# ser2can.net
KiCad netlist of a schematic drawn in EAGLE
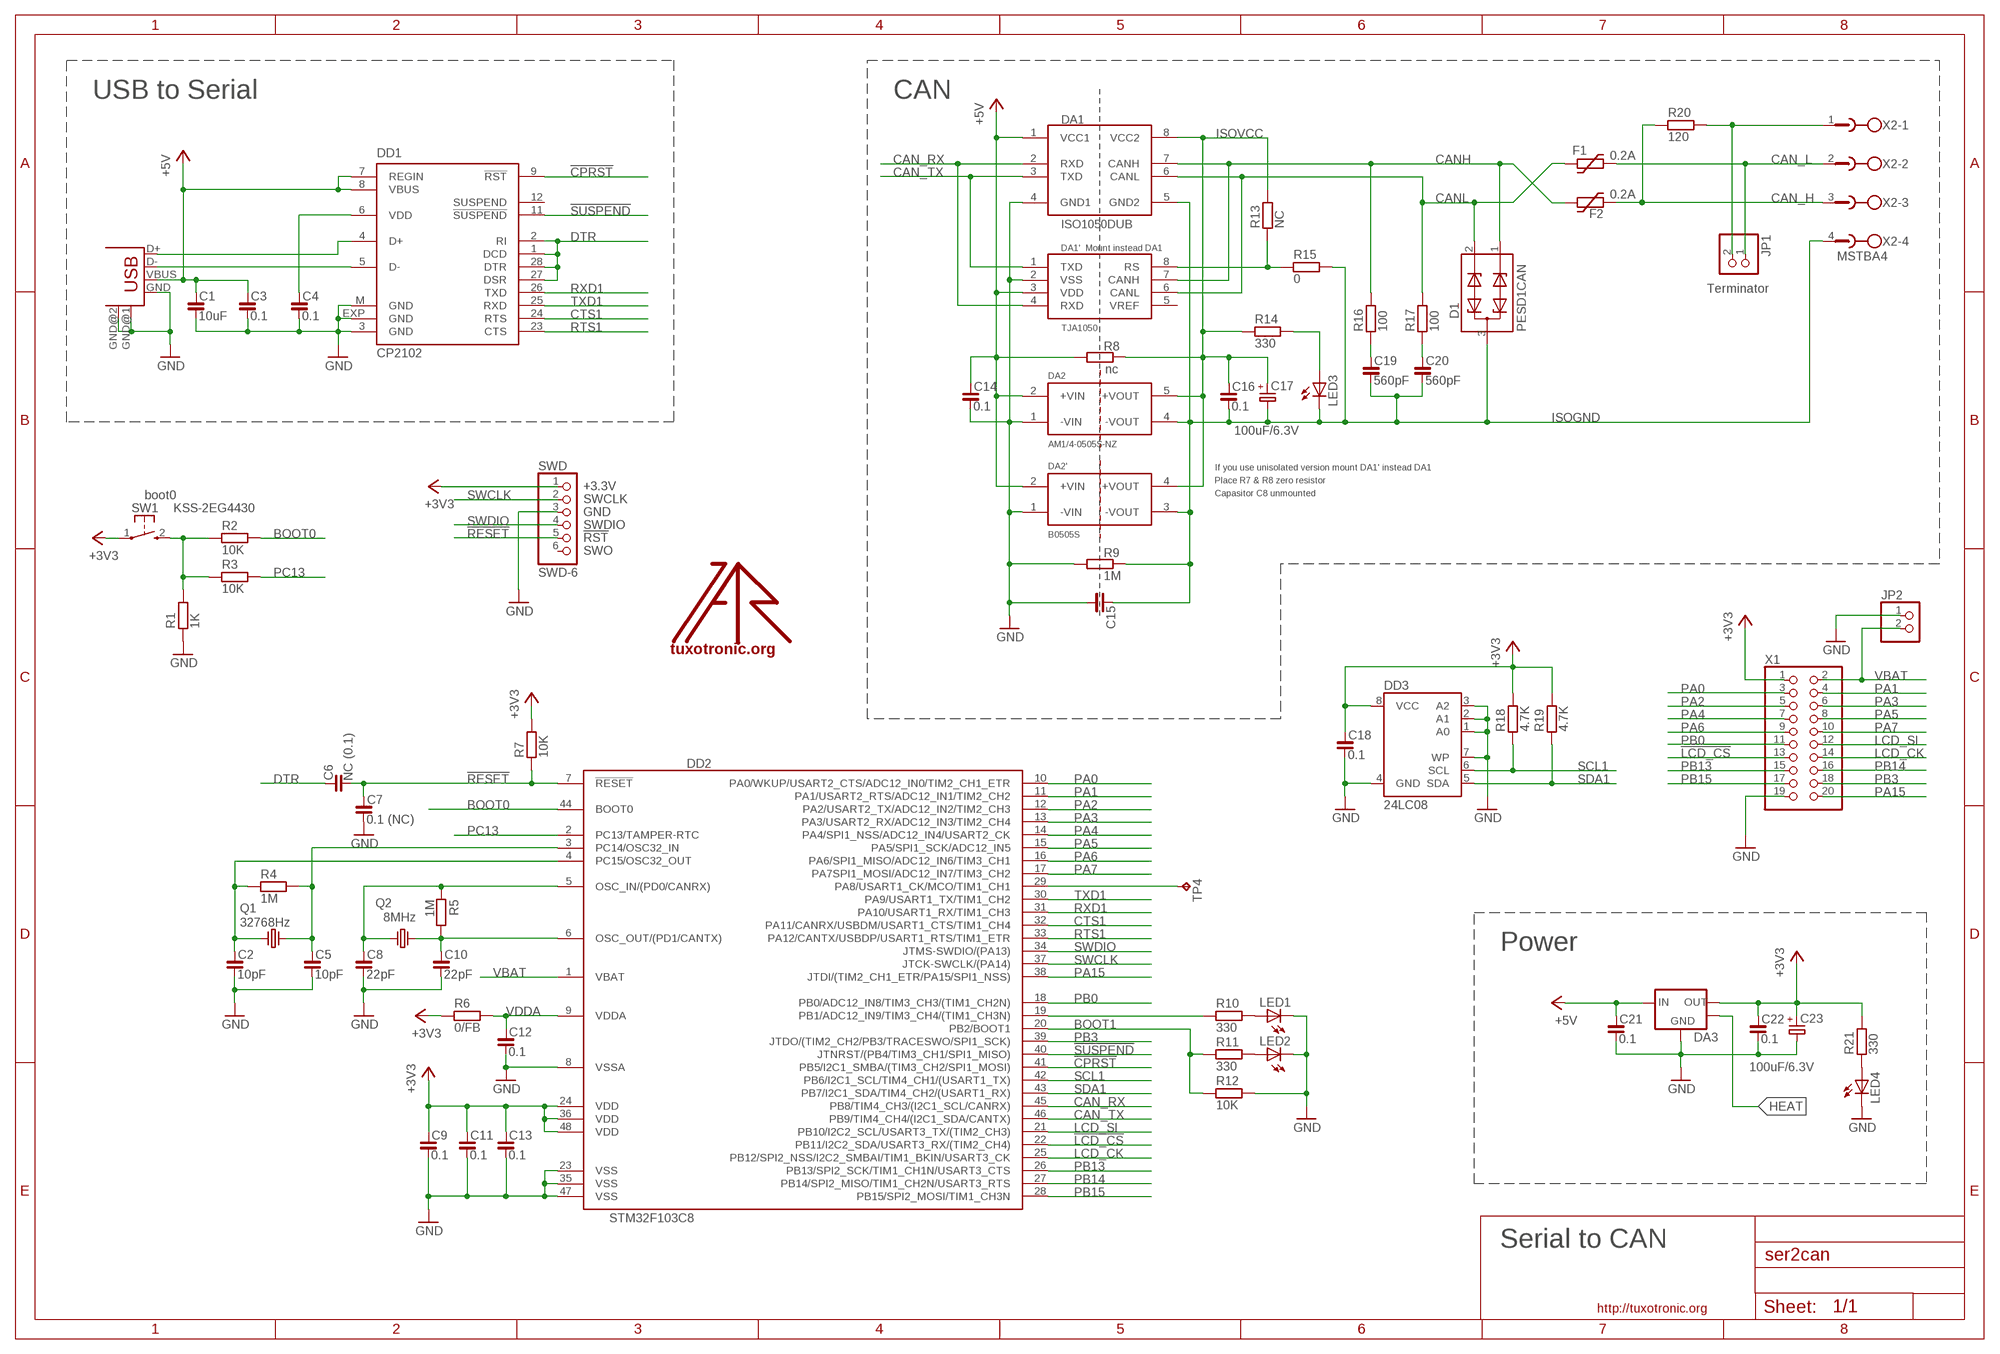
[diagram p0: schematic, sheet 1]

(export (version "E")
  (design (tool "Eeschema 10.0.6"))
  (components
    (comp (ref "C1")
      (value "10uF")
      (footprint "eagle-import:C0603")
      (libsource (lib "eagle-import") (part "rc-master-smd_C_0603"))
    )
    (comp (ref "C2")
      (value "10pF")
      (footprint "eagle-import:C0603")
      (libsource (lib "eagle-import") (part "rc-master-smd_C_0603"))
    )
    (comp (ref "C3")
      (value "0.1")
      (footprint "eagle-import:C0603")
      (libsource (lib "eagle-import") (part "rc-master-smd_C_0603"))
    )
    (comp (ref "C4")
      (value "0.1")
      (footprint "eagle-import:C0603")
      (libsource (lib "eagle-import") (part "rc-master-smd_C_0603"))
    )
    (comp (ref "C5")
      (value "10pF")
      (footprint "eagle-import:C0603")
      (libsource (lib "eagle-import") (part "rc-master-smd_C_0603"))
    )
    (comp (ref "C6")
      (value "NC (0.1)")
      (footprint "eagle-import:C0603")
      (libsource (lib "eagle-import") (part "rc-master-smd_C_0603"))
    )
    (comp (ref "C7")
      (value "0.1 (NC)")
      (footprint "eagle-import:C0603")
      (libsource (lib "eagle-import") (part "rc-master-smd_C_0603"))
    )
    (comp (ref "C8")
      (value "22pF")
      (footprint "eagle-import:C0603")
      (libsource (lib "eagle-import") (part "rc-master-smd_C_0603"))
    )
    (comp (ref "C9")
      (value "0.1")
      (footprint "eagle-import:C0603")
      (libsource (lib "eagle-import") (part "rc-master-smd_C_0603"))
    )
    (comp (ref "C10")
      (value "22pF")
      (footprint "eagle-import:C0603")
      (libsource (lib "eagle-import") (part "rc-master-smd_C_0603"))
    )
    (comp (ref "C11")
      (value "0.1")
      (footprint "eagle-import:C0603")
      (libsource (lib "eagle-import") (part "rc-master-smd_C_0603"))
    )
    (comp (ref "C12")
      (value "0.1")
      (footprint "eagle-import:C0603")
      (libsource (lib "eagle-import") (part "rc-master-smd_C_0603"))
    )
    (comp (ref "C13")
      (value "0.1")
      (footprint "eagle-import:C0603")
      (libsource (lib "eagle-import") (part "rc-master-smd_C_0603"))
    )
    (comp (ref "C14")
      (value "0.1")
      (footprint "eagle-import:C0603")
      (libsource (lib "eagle-import") (part "rc-master-smd_C_0603"))
    )
    (comp (ref "C15")
      (value "C_C050-110X055")
      (footprint "eagle-import:C050-110X055")
      (libsource (lib "eagle-import") (part "C_C050-110X055"))
    )
    (comp (ref "C16")
      (value "0.1")
      (footprint "eagle-import:C0603")
      (libsource (lib "eagle-import") (part "rc-master-smd_C_0603"))
    )
    (comp (ref "C17")
      (value "100uF/6.3V")
      (footprint "eagle-import:SMC_C")
      (libsource (lib "eagle-import") (part "CP_SMCC"))
    )
    (comp (ref "C18")
      (value "0.1")
      (footprint "eagle-import:C0603")
      (libsource (lib "eagle-import") (part "rc-master-smd_C_0603"))
    )
    (comp (ref "C19")
      (value "560pF")
      (footprint "eagle-import:C0603")
      (libsource (lib "eagle-import") (part "rc-master-smd_C_0603"))
    )
    (comp (ref "C20")
      (value "560pF")
      (footprint "eagle-import:C0603")
      (libsource (lib "eagle-import") (part "rc-master-smd_C_0603"))
    )
    (comp (ref "C21")
      (value "0.1")
      (footprint "eagle-import:C0805")
      (libsource (lib "eagle-import") (part "rc-master-smd_C_0805"))
    )
    (comp (ref "C22")
      (value "0.1")
      (footprint "eagle-import:C0805")
      (libsource (lib "eagle-import") (part "rc-master-smd_C_0805"))
    )
    (comp (ref "C23")
      (value "100uF/6.3V")
      (footprint "eagle-import:SMC_C")
      (libsource (lib "eagle-import") (part "CP_SMCC"))
    )
    (comp (ref "D1")
      (value "PESD1CAN")
      (footprint "eagle-import:SOT23")
      (libsource (lib "eagle-import") (part "PESD1CAN"))
    )
    (comp (ref "DA1")
      (value "ISO1050DUB")
      (footprint "eagle-import:DUB-8")
      (libsource (lib "eagle-import") (part "ISO1050DUB"))
    )
    (comp (ref "DA1'")
      (value "TJA1050")
      (footprint "eagle-import:SO08")
      (libsource (lib "eagle-import") (part "TJA1050"))
    )
    (comp (ref "DA2")
      (value "AM1/4-0505S-NZ")
      (footprint "eagle-import:AM1_4")
      (libsource (lib "eagle-import") (part "AM1/4--NZ0505S"))
    )
    (comp (ref "DA2'")
      (value "B0505S")
      (footprint "eagle-import:SIP4")
      (libsource (lib "eagle-import") (part "VA-S1"))
    )
    (comp (ref "DA3")
      (value "LM1117-3.3")
      (footprint "eagle-import:SOT223")
      (libsource (lib "eagle-import") (part "LM1117-3.3"))
    )
    (comp (ref "DD1")
      (value "CP2102")
      (footprint "eagle-import:MLP28")
      (libsource (lib "eagle-import") (part "CP2102"))
    )
    (comp (ref "DD2")
      (value "STM32F103C8")
      (footprint "eagle-import:LQFP48")
      (libsource (lib "eagle-import") (part "STM32F103C8"))
    )
    (comp (ref "DD3")
      (value "24LC08")
      (footprint "eagle-import:SO08")
      (libsource (lib "eagle-import") (part "AT24CS256"))
    )
    (comp (ref "F1")
      (value "0.2A")
      (footprint "eagle-import:1812L")
      (libsource (lib "eagle-import") (part "1812L"))
    )
    (comp (ref "F2")
      (value "0.2A")
      (footprint "eagle-import:1812L")
      (libsource (lib "eagle-import") (part "1812L"))
    )
    (comp (ref "JP1")
      (value "PINHD-1X2_2.54S")
      (footprint "eagle-import:1X02SMALL")
      (libsource (lib "eagle-import") (part "PINHD-1X2_2.54S"))
    )
    (comp (ref "JP2")
      (value "PINHD-1X2_2.00")
      (footprint "eagle-import:1X02M")
      (libsource (lib "eagle-import") (part "PINHD-1X2_2.00"))
    )
    (comp (ref "LED1")
      (value "LEDCHIPLED_0805")
      (footprint "eagle-import:CHIPLED_0805")
      (libsource (lib "eagle-import") (part "LEDCHIPLED_0805"))
    )
    (comp (ref "LED2")
      (value "LEDCHIPLED_0805")
      (footprint "eagle-import:CHIPLED_0805")
      (libsource (lib "eagle-import") (part "LEDCHIPLED_0805"))
    )
    (comp (ref "LED3")
      (value "LEDCHIPLED_0805")
      (footprint "eagle-import:CHIPLED_0805")
      (libsource (lib "eagle-import") (part "LEDCHIPLED_0805"))
    )
    (comp (ref "LED4")
      (value "LEDCHIPLED_0805")
      (footprint "eagle-import:CHIPLED_0805")
      (libsource (lib "eagle-import") (part "LEDCHIPLED_0805"))
    )
    (comp (ref "Q1")
      (value "32768Hz")
      (footprint "eagle-import:MM20SS")
      (libsource (lib "eagle-import") (part "CRYSTAL-MM20SS"))
    )
    (comp (ref "Q2")
      (value "8MHz")
      (footprint "eagle-import:HC49_S")
      (libsource (lib "eagle-import") (part "CRYSTAL-HC49S"))
    )
    (comp (ref "R1")
      (value "1K")
      (footprint "eagle-import:R0603")
      (libsource (lib "eagle-import") (part "R_0603"))
    )
    (comp (ref "R2")
      (value "10K")
      (footprint "eagle-import:R0603")
      (libsource (lib "eagle-import") (part "R_0603"))
    )
    (comp (ref "R3")
      (value "10K")
      (footprint "eagle-import:R0603")
      (libsource (lib "eagle-import") (part "R_0603"))
    )
    (comp (ref "R4")
      (value "1M")
      (footprint "eagle-import:R0603")
      (libsource (lib "eagle-import") (part "R_0603"))
    )
    (comp (ref "R5")
      (value "1M")
      (footprint "eagle-import:R0603")
      (libsource (lib "eagle-import") (part "R_0603"))
    )
    (comp (ref "R6")
      (value "0/FB")
      (footprint "eagle-import:R0603")
      (libsource (lib "eagle-import") (part "R_0603"))
    )
    (comp (ref "R7")
      (value "10K")
      (footprint "eagle-import:R0603")
      (libsource (lib "eagle-import") (part "R_0603"))
    )
    (comp (ref "R8")
      (value "nc")
      (footprint "eagle-import:R1206")
      (libsource (lib "eagle-import") (part "R_1206"))
    )
    (comp (ref "R9")
      (value "1M")
      (footprint "eagle-import:R1206")
      (libsource (lib "eagle-import") (part "R_1206"))
    )
    (comp (ref "R10")
      (value "330")
      (footprint "eagle-import:R0603")
      (libsource (lib "eagle-import") (part "R_0603"))
    )
    (comp (ref "R11")
      (value "330")
      (footprint "eagle-import:R0603")
      (libsource (lib "eagle-import") (part "R_0603"))
    )
    (comp (ref "R12")
      (value "10K")
      (footprint "eagle-import:R0603")
      (libsource (lib "eagle-import") (part "R_0603"))
    )
    (comp (ref "R13")
      (value "NC")
      (footprint "eagle-import:R0603")
      (libsource (lib "eagle-import") (part "R_0603"))
    )
    (comp (ref "R14")
      (value "330")
      (footprint "eagle-import:R0603")
      (libsource (lib "eagle-import") (part "R_0603"))
    )
    (comp (ref "R15")
      (value "0")
      (footprint "eagle-import:R0603")
      (libsource (lib "eagle-import") (part "R_0603"))
    )
    (comp (ref "R16")
      (value "100")
      (footprint "eagle-import:R0603")
      (libsource (lib "eagle-import") (part "R_0603"))
    )
    (comp (ref "R17")
      (value "100")
      (footprint "eagle-import:R0603")
      (libsource (lib "eagle-import") (part "R_0603"))
    )
    (comp (ref "R18")
      (value "4.7K")
      (footprint "eagle-import:R0603")
      (libsource (lib "eagle-import") (part "R_0603"))
    )
    (comp (ref "R19")
      (value "4.7K")
      (footprint "eagle-import:R0603")
      (libsource (lib "eagle-import") (part "R_0603"))
    )
    (comp (ref "R20")
      (value "120")
      (footprint "eagle-import:R0805")
      (libsource (lib "eagle-import") (part "R_0805"))
    )
    (comp (ref "R21")
      (value "330")
      (footprint "eagle-import:R0603")
      (libsource (lib "eagle-import") (part "R_0603"))
    )
    (comp (ref "SW1")
      (value "KSS-2EG4430")
      (footprint "eagle-import:KSS-2EG4430")
      (libsource (lib "eagle-import") (part "KSS-2EG4430"))
    )
    (comp (ref "SWD")
      (value "SWD-6")
      (footprint "eagle-import:JTAG6PIN")
      (libsource (lib "eagle-import") (part "SWD-6"))
    )
    (comp (ref "TP4")
      (value "TPB1,27")
      (footprint "eagle-import:B1,27")
      (libsource (lib "eagle-import") (part "TPB1,27"))
    )
    (comp (ref "U$")
      (value "LOGO")
      (footprint "eagle-import:TT_LOGO")
      (libsource (lib "eagle-import") (part "LOGO"))
    )
    (comp (ref "USB1")
      (value "USB-B-H")
      (footprint "eagle-import:USB-B-H")
      (libsource (lib "eagle-import") (part "USB-B-H"))
    )
    (comp (ref "X1")
      (value "PINHD-2X10_2.54")
      (footprint "eagle-import:2X10")
      (libsource (lib "eagle-import") (part "PINHD-2X10_2.54"))
    )
    (comp (ref "X2")
      (value "MSTBA4")
      (footprint "eagle-import:MSTBA4")
      (libsource (lib "eagle-import") (part "MSTBA4"))
    )
  )
  (nets
    (net (code "1") (name "+3V3") (class "Default")
      (node (ref "C11") (pin "1") (pinfunction "1_1") (pintype "passive"))
      (node (ref "C13") (pin "1") (pinfunction "1_1") (pintype "passive"))
      (node (ref "C18") (pin "1") (pinfunction "1_1") (pintype "passive"))
      (node (ref "C22") (pin "1") (pinfunction "1_1") (pintype "passive"))
      (node (ref "C23") (pin "+") (pinfunction "+_+") (pintype "passive"))
      (node (ref "C9") (pin "1") (pinfunction "1_1") (pintype "passive"))
      (node (ref "DA3") (pin "2") (pinfunction "OUT_2") (pintype "output"))
      (node (ref "DD2") (pin "24") (pinfunction "VDD_24") (pintype "power_in"))
      (node (ref "DD2") (pin "36") (pinfunction "VDD_36") (pintype "power_in"))
      (node (ref "DD2") (pin "48") (pinfunction "VDD_48") (pintype "power_in"))
      (node (ref "DD3") (pin "8") (pinfunction "VCC_8") (pintype "power_in"))
      (node (ref "R18") (pin "2") (pinfunction "2_2") (pintype "passive"))
      (node (ref "R19") (pin "2") (pinfunction "2_2") (pintype "passive"))
      (node (ref "R21") (pin "2") (pinfunction "2_2") (pintype "passive"))
      (node (ref "R6") (pin "1") (pinfunction "1_1") (pintype "passive"))
      (node (ref "R7") (pin "2") (pinfunction "2_2") (pintype "passive"))
      (node (ref "SW1") (pin "1") (pinfunction "P_1") (pintype "passive"))
      (node (ref "SWD") (pin "1") (pinfunction "1_1") (pintype "passive"))
      (node (ref "X1") (pin "1") (pinfunction "1_1") (pintype "passive"))
    )
    (net (code "2") (name "+5V") (class "Default")
      (node (ref "C1") (pin "1") (pinfunction "1_1") (pintype "passive"))
      (node (ref "C14") (pin "1") (pinfunction "1_1") (pintype "passive"))
      (node (ref "C21") (pin "1") (pinfunction "1_1") (pintype "passive"))
      (node (ref "C3") (pin "1") (pinfunction "1_1") (pintype "passive"))
      (node (ref "DA1") (pin "1") (pinfunction "VCC1_1") (pintype "power_in"))
      (node (ref "DA1'") (pin "3") (pinfunction "VDD_3") (pintype "power_in"))
      (node (ref "DA2") (pin "2") (pinfunction "+VIN_2") (pintype "power_in"))
      (node (ref "DA2'") (pin "2") (pinfunction "+VIN_2") (pintype "power_in"))
      (node (ref "DA3") (pin "3") (pinfunction "IN_3") (pintype "power_in"))
      (node (ref "DD1") (pin "7") (pinfunction "REGIN_7") (pintype "passive"))
      (node (ref "DD1") (pin "8") (pinfunction "VBUS_8") (pintype "input"))
      (node (ref "R8") (pin "1") (pinfunction "1_1") (pintype "passive"))
      (node (ref "USB1") (pin "VBUS") (pinfunction "VBUS_VBUS") (pintype "bidirectional"))
    )
    (net (code "3") (name "/BOOT0") (class "Default")
      (node (ref "DD2") (pin "44") (pinfunction "BOOT0_44") (pintype "input"))
      (node (ref "R2") (pin "2") (pinfunction "2_2") (pintype "passive"))
    )
    (net (code "4") (name "/BOOT1") (class "Default")
      (node (ref "DD2") (pin "20") (pinfunction "PB2/BOOT1_20") (pintype "bidirectional"))
      (node (ref "R11") (pin "1") (pinfunction "1_1") (pintype "passive"))
      (node (ref "R12") (pin "1") (pinfunction "1_1") (pintype "passive"))
    )
    (net (code "5") (name "/CANH") (class "Default")
      (node (ref "D1") (pin "1") (pinfunction "1_1") (pintype "passive"))
      (node (ref "DA1") (pin "7") (pinfunction "CANH_7") (pintype "bidirectional"))
      (node (ref "DA1'") (pin "7") (pinfunction "CANH_7") (pintype "bidirectional"))
      (node (ref "F2") (pin "P$1") (pinfunction "1_P$1") (pintype "passive"))
      (node (ref "R16") (pin "2") (pinfunction "2_2") (pintype "passive"))
    )
    (net (code "6") (name "/CANL") (class "Default")
      (node (ref "D1") (pin "2") (pinfunction "2_2") (pintype "passive"))
      (node (ref "DA1") (pin "6") (pinfunction "CANL_6") (pintype "bidirectional"))
      (node (ref "DA1'") (pin "6") (pinfunction "CANL_6") (pintype "bidirectional"))
      (node (ref "F1") (pin "P$1") (pinfunction "1_P$1") (pintype "passive"))
      (node (ref "R17") (pin "2") (pinfunction "2_2") (pintype "passive"))
    )
    (net (code "7") (name "/CAN_H") (class "Default")
      (node (ref "F2") (pin "P$2") (pinfunction "2_P$2") (pintype "passive"))
      (node (ref "R20") (pin "1") (pinfunction "1_1") (pintype "passive"))
      (node (ref "X2") (pin "3") (pinfunction "1_3") (pintype "passive"))
    )
    (net (code "8") (name "/CAN_L") (class "Default")
      (node (ref "F1") (pin "P$2") (pinfunction "2_P$2") (pintype "passive"))
      (node (ref "JP1") (pin "1") (pinfunction "1_1") (pintype "passive"))
      (node (ref "X2") (pin "2") (pinfunction "1_2") (pintype "passive"))
    )
    (net (code "9") (name "/CAN_RX") (class "Default")
      (node (ref "DA1") (pin "2") (pinfunction "RXD_2") (pintype "output"))
      (node (ref "DA1'") (pin "4") (pinfunction "RXD_4") (pintype "output"))
      (node (ref "DD2") (pin "45") (pinfunction "PB8/TIM4_CH3/(I2C1_SCL/CANRX)_45") (pintype "bidirectional"))
    )
    (net (code "10") (name "/CAN_TX") (class "Default")
      (node (ref "DA1") (pin "3") (pinfunction "TXD_3") (pintype "input"))
      (node (ref "DA1'") (pin "1") (pinfunction "TXD_1") (pintype "input"))
      (node (ref "DD2") (pin "46") (pinfunction "PB9/TIM4_CH4/(I2C1_SDA/CANTX)_46") (pintype "bidirectional"))
    )
    (net (code "11") (name "/CTS1") (class "Default")
      (node (ref "DD1") (pin "24") (pinfunction "RTS_24") (pintype "output"))
      (node (ref "DD2") (pin "32") (pinfunction "PA11/CANRX/USBDM/USART1_CTS/TIM1_CH4_32") (pintype "bidirectional"))
    )
    (net (code "12") (name "/DTR") (class "Default")
      (node (ref "C6") (pin "1") (pinfunction "1_1") (pintype "passive"))
      (node (ref "DD1") (pin "1") (pinfunction "DCD_1") (pintype "input"))
      (node (ref "DD1") (pin "2") (pinfunction "RI_2") (pintype "input"))
      (node (ref "DD1") (pin "27") (pinfunction "DSR_27") (pintype "input"))
      (node (ref "DD1") (pin "28") (pinfunction "DTR_28") (pintype "output"))
    )
    (net (code "13") (name "/ISOGND") (class "Default")
      (node (ref "C15") (pin "1") (pinfunction "1_1") (pintype "passive"))
      (node (ref "C16") (pin "2") (pinfunction "2_2") (pintype "passive"))
      (node (ref "C17") (pin "-") (pinfunction "-_-") (pintype "passive"))
      (node (ref "C19") (pin "2") (pinfunction "2_2") (pintype "passive"))
      (node (ref "C20") (pin "2") (pinfunction "2_2") (pintype "passive"))
      (node (ref "D1") (pin "3") (pinfunction "3_3") (pintype "passive"))
      (node (ref "DA1") (pin "5") (pinfunction "GND2_5") (pintype "power_in"))
      (node (ref "DA2") (pin "4") (pinfunction "-VOUT_4") (pintype "passive"))
      (node (ref "DA2'") (pin "3") (pinfunction "-VOUT_3") (pintype "passive"))
      (node (ref "LED3") (pin "C") (pinfunction "C_C") (pintype "passive"))
      (node (ref "R15") (pin "2") (pinfunction "2_2") (pintype "passive"))
      (node (ref "R9") (pin "2") (pinfunction "2_2") (pintype "passive"))
      (node (ref "X2") (pin "4") (pinfunction "1_4") (pintype "passive"))
    )
    (net (code "14") (name "/ISOVCC") (class "Default")
      (node (ref "C16") (pin "1") (pinfunction "1_1") (pintype "passive"))
      (node (ref "C17") (pin "+") (pinfunction "+_+") (pintype "passive"))
      (node (ref "DA1") (pin "8") (pinfunction "VCC2_8") (pintype "power_in"))
      (node (ref "DA2") (pin "5") (pinfunction "+VOUT_5") (pintype "passive"))
      (node (ref "DA2'") (pin "4") (pinfunction "+VOUT_4") (pintype "passive"))
      (node (ref "R13") (pin "2") (pinfunction "2_2") (pintype "passive"))
      (node (ref "R14") (pin "1") (pinfunction "1_1") (pintype "passive"))
      (node (ref "R8") (pin "2") (pinfunction "2_2") (pintype "passive"))
    )
    (net (code "15") (name "/LCD_CK") (class "Default")
      (node (ref "DD2") (pin "25") (pinfunction "PB12/SPI2_NSS/I2C2_SMBAI/TIM1_BKIN/USART3_CK_25") (pintype "bidirectional"))
      (node (ref "X1") (pin "14") (pinfunction "14_14") (pintype "passive"))
    )
    (net (code "16") (name "/LCD_SI") (class "Default")
      (node (ref "DD2") (pin "21") (pinfunction "PB10/I2C2_SCL/USART3_TX/(TIM2_CH3)_21") (pintype "bidirectional"))
      (node (ref "X1") (pin "12") (pinfunction "12_12") (pintype "passive"))
    )
    (net (code "17") (name "/PA0") (class "Default")
      (node (ref "DD2") (pin "10") (pinfunction "PA0/WKUP/USART2_CTS/ADC12_IN0/TIM2_CH1_ETR_10") (pintype "bidirectional"))
      (node (ref "X1") (pin "3") (pinfunction "3_3") (pintype "passive"))
    )
    (net (code "18") (name "/PA1") (class "Default")
      (node (ref "DD2") (pin "11") (pinfunction "PA1/USART2_RTS/ADC12_IN1/TIM2_CH2_11") (pintype "bidirectional"))
      (node (ref "X1") (pin "4") (pinfunction "4_4") (pintype "passive"))
    )
    (net (code "19") (name "/PA2") (class "Default")
      (node (ref "DD2") (pin "12") (pinfunction "PA2/USART2_TX/ADC12_IN2/TIM2_CH3_12") (pintype "bidirectional"))
      (node (ref "X1") (pin "5") (pinfunction "5_5") (pintype "passive"))
    )
    (net (code "20") (name "/PA3") (class "Default")
      (node (ref "DD2") (pin "13") (pinfunction "PA3/USART2_RX/ADC12_IN3/TIM2_CH4_13") (pintype "bidirectional"))
      (node (ref "X1") (pin "6") (pinfunction "6_6") (pintype "passive"))
    )
    (net (code "21") (name "/PA4") (class "Default")
      (node (ref "DD2") (pin "14") (pinfunction "PA4/SPI1_NSS/ADC12_IN4/USART2_CK_14") (pintype "bidirectional"))
      (node (ref "X1") (pin "7") (pinfunction "7_7") (pintype "passive"))
    )
    (net (code "22") (name "/PA5") (class "Default")
      (node (ref "DD2") (pin "15") (pinfunction "PA5/SPI1_SCK/ADC12_IN5_15") (pintype "bidirectional"))
      (node (ref "X1") (pin "8") (pinfunction "8_8") (pintype "passive"))
    )
    (net (code "23") (name "/PA6") (class "Default")
      (node (ref "DD2") (pin "16") (pinfunction "PA6/SPI1_MISO/ADC12_IN6/TIM3_CH1_16") (pintype "bidirectional"))
      (node (ref "X1") (pin "9") (pinfunction "9_9") (pintype "passive"))
    )
    (net (code "24") (name "/PA7") (class "Default")
      (node (ref "DD2") (pin "17") (pinfunction "PA7SPI1_MOSI/ADC12_IN7/TIM3_CH2_17") (pintype "bidirectional"))
      (node (ref "X1") (pin "10") (pinfunction "10_10") (pintype "passive"))
    )
    (net (code "25") (name "/PA15") (class "Default")
      (node (ref "DD2") (pin "38") (pinfunction "JTDI/(TIM2_CH1_ETR/PA15/SPI1_NSS)_38") (pintype "bidirectional"))
      (node (ref "X1") (pin "20") (pinfunction "20_20") (pintype "passive"))
    )
    (net (code "26") (name "/PB0") (class "Default")
      (node (ref "DD2") (pin "18") (pinfunction "PB0/ADC12_IN8/TIM3_CH3/(TIM1_CH2N)_18") (pintype "bidirectional"))
      (node (ref "X1") (pin "11") (pinfunction "11_11") (pintype "passive"))
    )
    (net (code "27") (name "/PB3") (class "Default")
      (node (ref "DD2") (pin "39") (pinfunction "JTDO/(TIM2_CH2/PB3/TRACESWO/SPI1_SCK)_39") (pintype "bidirectional"))
      (node (ref "X1") (pin "18") (pinfunction "18_18") (pintype "passive"))
    )
    (net (code "28") (name "/PB13") (class "Default")
      (node (ref "DD2") (pin "26") (pinfunction "PB13/SPI2_SCK/TIM1_CH1N/USART3_CTS_26") (pintype "bidirectional"))
      (node (ref "X1") (pin "15") (pinfunction "15_15") (pintype "passive"))
    )
    (net (code "29") (name "/PB14") (class "Default")
      (node (ref "DD2") (pin "27") (pinfunction "PB14/SPI2_MISO/TIM1_CH2N/USART3_RTS_27") (pintype "bidirectional"))
      (node (ref "X1") (pin "16") (pinfunction "16_16") (pintype "passive"))
    )
    (net (code "30") (name "/PB15") (class "Default")
      (node (ref "DD2") (pin "28") (pinfunction "PB15/SPI2_MOSI/TIM1_CH3N_28") (pintype "bidirectional"))
      (node (ref "X1") (pin "17") (pinfunction "17_17") (pintype "passive"))
    )
    (net (code "31") (name "/PC13") (class "Default")
      (node (ref "DD2") (pin "2") (pinfunction "PC13/TAMPER-RTC_2") (pintype "bidirectional"))
      (node (ref "R3") (pin "2") (pinfunction "2_2") (pintype "passive"))
    )
    (net (code "32") (name "/RTS1") (class "Default")
      (node (ref "DD1") (pin "23") (pinfunction "CTS_23") (pintype "input"))
      (node (ref "DD2") (pin "33") (pinfunction "PA12/CANTX/USBDP/USART1_RTS/TIM1_ETR_33") (pintype "bidirectional"))
    )
    (net (code "33") (name "/RXD1") (class "Default")
      (node (ref "DD1") (pin "26") (pinfunction "TXD_26") (pintype "output"))
      (node (ref "DD2") (pin "31") (pinfunction "PA10/USART1_RX/TIM1_CH3_31") (pintype "bidirectional"))
    )
    (net (code "34") (name "/SCL1") (class "Default")
      (node (ref "DD2") (pin "42") (pinfunction "PB6/I2C1_SCL/TIM4_CH1/(USART1_TX)_42") (pintype "bidirectional"))
      (node (ref "DD3") (pin "6") (pinfunction "SCL_6") (pintype "bidirectional"))
      (node (ref "R18") (pin "1") (pinfunction "1_1") (pintype "passive"))
    )
    (net (code "35") (name "/SDA1") (class "Default")
      (node (ref "DD2") (pin "43") (pinfunction "PB7/I2C1_SDA/TIM4_CH2/(USART1_RX)_43") (pintype "bidirectional"))
      (node (ref "DD3") (pin "5") (pinfunction "SDA_5") (pintype "bidirectional"))
      (node (ref "R19") (pin "1") (pinfunction "1_1") (pintype "passive"))
    )
    (net (code "36") (name "/SWCLK") (class "Default")
      (node (ref "DD2") (pin "37") (pinfunction "JTCK-SWCLK/(PA14)_37") (pintype "bidirectional"))
      (node (ref "SWD") (pin "2") (pinfunction "2_2") (pintype "passive"))
    )
    (net (code "37") (name "/SWDIO") (class "Default")
      (node (ref "DD2") (pin "34") (pinfunction "JTMS-SWDIO/(PA13)_34") (pintype "bidirectional"))
      (node (ref "SWD") (pin "4") (pinfunction "4_4") (pintype "passive"))
    )
    (net (code "38") (name "/TXD1") (class "Default")
      (node (ref "DD1") (pin "25") (pinfunction "RXD_25") (pintype "input"))
      (node (ref "DD2") (pin "30") (pinfunction "PA9/USART1_TX/TIM1_CH2_30") (pintype "bidirectional"))
    )
    (net (code "39") (name "/VBAT") (class "Default")
      (node (ref "DD2") (pin "1") (pinfunction "VBAT_1") (pintype "power_in"))
      (node (ref "JP2") (pin "2") (pinfunction "2_2") (pintype "passive"))
      (node (ref "X1") (pin "2") (pinfunction "2_2") (pintype "passive"))
    )
    (net (code "40") (name "/VDDA") (class "Default")
      (node (ref "C12") (pin "1") (pinfunction "1_1") (pintype "passive"))
      (node (ref "DD2") (pin "9") (pinfunction "VDDA_9") (pintype "power_in"))
      (node (ref "R6") (pin "2") (pinfunction "2_2") (pintype "passive"))
    )
    (net (code "41") (name "/~{CPRST}") (class "Default")
      (node (ref "DD1") (pin "9") (pinfunction "~{RST}_9") (pintype "bidirectional"))
      (node (ref "DD2") (pin "41") (pinfunction "PB5/I2C1_SMBA/(TIM3_CH2/SPI1_MOSI)_41") (pintype "bidirectional"))
    )
    (net (code "42") (name "/~{LCD_CS}") (class "Default")
      (node (ref "DD2") (pin "22") (pinfunction "PB11/I2C2_SDA/USART3_RX/(TIM2_CH4)_22") (pintype "bidirectional"))
      (node (ref "X1") (pin "13") (pinfunction "13_13") (pintype "passive"))
    )
    (net (code "43") (name "/~{RESET}") (class "Default")
      (node (ref "C6") (pin "2") (pinfunction "2_2") (pintype "passive"))
      (node (ref "C7") (pin "1") (pinfunction "1_1") (pintype "passive"))
      (node (ref "DD2") (pin "7") (pinfunction "~{RESET}_7") (pintype "input"))
      (node (ref "R7") (pin "1") (pinfunction "1_1") (pintype "passive"))
      (node (ref "SWD") (pin "5") (pinfunction "5_5") (pintype "passive"))
    )
    (net (code "44") (name "/~{SUSPEND}") (class "Default")
      (node (ref "DD1") (pin "11") (pinfunction "~{SUSPEND}_11") (pintype "output"))
      (node (ref "DD2") (pin "40") (pinfunction "JTNRST/(PB4/TIM3_CH1/SPI1_MISO)_40") (pintype "bidirectional"))
    )
    (net (code "45") (name "GND") (class "Default")
      (node (ref "C1") (pin "2") (pinfunction "2_2") (pintype "passive"))
      (node (ref "C10") (pin "2") (pinfunction "2_2") (pintype "passive"))
      (node (ref "C11") (pin "2") (pinfunction "2_2") (pintype "passive"))
      (node (ref "C12") (pin "2") (pinfunction "2_2") (pintype "passive"))
      (node (ref "C13") (pin "2") (pinfunction "2_2") (pintype "passive"))
      (node (ref "C14") (pin "2") (pinfunction "2_2") (pintype "passive"))
      (node (ref "C15") (pin "2") (pinfunction "2_2") (pintype "passive"))
      (node (ref "C18") (pin "2") (pinfunction "2_2") (pintype "passive"))
      (node (ref "C2") (pin "2") (pinfunction "2_2") (pintype "passive"))
      (node (ref "C21") (pin "2") (pinfunction "2_2") (pintype "passive"))
      (node (ref "C22") (pin "2") (pinfunction "2_2") (pintype "passive"))
      (node (ref "C23") (pin "-") (pinfunction "-_-") (pintype "passive"))
      (node (ref "C3") (pin "2") (pinfunction "2_2") (pintype "passive"))
      (node (ref "C4") (pin "2") (pinfunction "2_2") (pintype "passive"))
      (node (ref "C5") (pin "2") (pinfunction "2_2") (pintype "passive"))
      (node (ref "C7") (pin "2") (pinfunction "2_2") (pintype "passive"))
      (node (ref "C8") (pin "2") (pinfunction "2_2") (pintype "passive"))
      (node (ref "C9") (pin "2") (pinfunction "2_2") (pintype "passive"))
      (node (ref "DA1") (pin "4") (pinfunction "GND1_4") (pintype "power_in"))
      (node (ref "DA1'") (pin "2") (pinfunction "VSS_2") (pintype "power_in"))
      (node (ref "DA2") (pin "1") (pinfunction "-VIN_1") (pintype "power_in"))
      (node (ref "DA2'") (pin "1") (pinfunction "-VIN_1") (pintype "power_in"))
      (node (ref "DA3") (pin "1") (pinfunction "GND_1") (pintype "power_in"))
      (node (ref "DD1") (pin "3") (pinfunction "GND_3") (pintype "power_in"))
      (node (ref "DD1") (pin "EXP") (pinfunction "GND_EXP") (pintype "power_in"))
      (node (ref "DD1") (pin "M") (pinfunction "GND_M") (pintype "power_in"))
      (node (ref "DD2") (pin "23") (pinfunction "VSS_23") (pintype "power_in"))
      (node (ref "DD2") (pin "35") (pinfunction "VSS_35") (pintype "power_in"))
      (node (ref "DD2") (pin "47") (pinfunction "VSS_47") (pintype "power_in"))
      (node (ref "DD2") (pin "8") (pinfunction "VSSA_8") (pintype "power_in"))
      (node (ref "DD3") (pin "1") (pinfunction "A0_1") (pintype "input"))
      (node (ref "DD3") (pin "2") (pinfunction "A1_2") (pintype "input"))
      (node (ref "DD3") (pin "3") (pinfunction "A2_3") (pintype "input"))
      (node (ref "DD3") (pin "4") (pinfunction "GND_4") (pintype "power_in"))
      (node (ref "DD3") (pin "7") (pinfunction "WP_7") (pintype "input"))
      (node (ref "JP2") (pin "1") (pinfunction "1_1") (pintype "passive"))
      (node (ref "LED1") (pin "C") (pinfunction "C_C") (pintype "passive"))
      (node (ref "LED2") (pin "C") (pinfunction "C_C") (pintype "passive"))
      (node (ref "LED4") (pin "C") (pinfunction "C_C") (pintype "passive"))
      (node (ref "R1") (pin "1") (pinfunction "1_1") (pintype "passive"))
      (node (ref "R12") (pin "2") (pinfunction "2_2") (pintype "passive"))
      (node (ref "R9") (pin "1") (pinfunction "1_1") (pintype "passive"))
      (node (ref "SWD") (pin "3") (pinfunction "3_3") (pintype "passive"))
      (node (ref "USB1") (pin "GND") (pinfunction "GND_GND") (pintype "bidirectional"))
      (node (ref "USB1") (pin "GND@1") (pinfunction "GND_GND@1") (pintype "bidirectional"))
      (node (ref "USB1") (pin "GND@2") (pinfunction "GND_GND@2") (pintype "bidirectional"))
      (node (ref "X1") (pin "19") (pinfunction "19_19") (pintype "passive"))
    )
    (net (code "46") (name "HEAT") (class "Default")
      (node (ref "DA3") (pin "4") (pinfunction "MASS_4") (pintype "passive"))
    )
    (net (code "47") (name "Net-(C19-Pad1)") (class "Default")
      (node (ref "C19") (pin "1") (pinfunction "1_1") (pintype "passive"))
      (node (ref "R16") (pin "1") (pinfunction "1_1") (pintype "passive"))
    )
    (net (code "48") (name "Net-(C20-Pad1)") (class "Default")
      (node (ref "C20") (pin "1") (pinfunction "1_1") (pintype "passive"))
      (node (ref "R17") (pin "1") (pinfunction "1_1") (pintype "passive"))
    )
    (net (code "49") (name "Net-(DA1'-RS)") (class "Default")
      (node (ref "DA1'") (pin "8") (pinfunction "RS_8") (pintype "input"))
      (node (ref "R13") (pin "1") (pinfunction "1_1") (pintype "passive"))
      (node (ref "R15") (pin "1") (pinfunction "1_1") (pintype "passive"))
    )
    (net (code "50") (name "Net-(DD1-D+)") (class "Default")
      (node (ref "DD1") (pin "4") (pinfunction "D+_4") (pintype "bidirectional"))
      (node (ref "USB1") (pin "D+") (pinfunction "D+_D+") (pintype "bidirectional"))
    )
    (net (code "51") (name "Net-(DD1-D-)") (class "Default")
      (node (ref "DD1") (pin "5") (pinfunction "D-_5") (pintype "bidirectional"))
      (node (ref "USB1") (pin "D-") (pinfunction "D-_D-") (pintype "bidirectional"))
    )
    (net (code "52") (name "Net-(DD1-VDD)") (class "Default")
      (node (ref "C4") (pin "1") (pinfunction "1_1") (pintype "passive"))
      (node (ref "DD1") (pin "6") (pinfunction "VDD_6") (pintype "power_in"))
    )
    (net (code "53") (name "Net-(DD2-OSC_IN{slash}(PD0{slash}CANRX))") (class "Default")
      (node (ref "C8") (pin "1") (pinfunction "1_1") (pintype "passive"))
      (node (ref "DD2") (pin "5") (pinfunction "OSC_IN/(PD0/CANRX)_5") (pintype "input"))
      (node (ref "Q2") (pin "1") (pinfunction "1_1") (pintype "passive"))
      (node (ref "R5") (pin "1") (pinfunction "1_1") (pintype "passive"))
    )
    (net (code "54") (name "Net-(DD2-OSC_OUT{slash}(PD1{slash}CANTX))") (class "Default")
      (node (ref "C10") (pin "1") (pinfunction "1_1") (pintype "passive"))
      (node (ref "DD2") (pin "6") (pinfunction "OSC_OUT/(PD1/CANTX)_6") (pintype "output"))
      (node (ref "Q2") (pin "2") (pinfunction "2_2") (pintype "passive"))
      (node (ref "R5") (pin "2") (pinfunction "2_2") (pintype "passive"))
    )
    (net (code "55") (name "Net-(DD2-PA8{slash}USART1_CK{slash}MCO{slash}TIM1_CH1)") (class "Default")
      (node (ref "DD2") (pin "29") (pinfunction "PA8/USART1_CK/MCO/TIM1_CH1_29") (pintype "bidirectional"))
      (node (ref "TP4") (pin "PP") (pinfunction "TP_PP") (pintype "input"))
    )
    (net (code "56") (name "Net-(DD2-PB1{slash}ADC12_IN9{slash}TIM3_CH4{slash}(TIM1_CH3N))") (class "Default")
      (node (ref "DD2") (pin "19") (pinfunction "PB1/ADC12_IN9/TIM3_CH4/(TIM1_CH3N)_19") (pintype "bidirectional"))
      (node (ref "R10") (pin "1") (pinfunction "1_1") (pintype "passive"))
    )
    (net (code "57") (name "Net-(DD2-PC14{slash}OSC32_IN)") (class "Default")
      (node (ref "C5") (pin "1") (pinfunction "1_1") (pintype "passive"))
      (node (ref "DD2") (pin "3") (pinfunction "PC14/OSC32_IN_3") (pintype "bidirectional"))
      (node (ref "Q1") (pin "4") (pinfunction "2_4") (pintype "passive"))
      (node (ref "R4") (pin "2") (pinfunction "2_2") (pintype "passive"))
    )
    (net (code "58") (name "Net-(DD2-PC15{slash}OSC32_OUT)") (class "Default")
      (node (ref "C2") (pin "1") (pinfunction "1_1") (pintype "passive"))
      (node (ref "DD2") (pin "4") (pinfunction "PC15/OSC32_OUT_4") (pintype "bidirectional"))
      (node (ref "Q1") (pin "1") (pinfunction "1_1") (pintype "passive"))
      (node (ref "R4") (pin "1") (pinfunction "1_1") (pintype "passive"))
    )
    (net (code "59") (name "Net-(JP1-Pad2)") (class "Default")
      (node (ref "JP1") (pin "2") (pinfunction "2_2") (pintype "passive"))
      (node (ref "R20") (pin "2") (pinfunction "2_2") (pintype "passive"))
      (node (ref "X2") (pin "1") (pinfunction "1_1") (pintype "passive"))
    )
    (net (code "60") (name "Net-(LED1-PadA)") (class "Default")
      (node (ref "LED1") (pin "A") (pinfunction "A_A") (pintype "passive"))
      (node (ref "R10") (pin "2") (pinfunction "2_2") (pintype "passive"))
    )
    (net (code "61") (name "Net-(LED2-PadA)") (class "Default")
      (node (ref "LED2") (pin "A") (pinfunction "A_A") (pintype "passive"))
      (node (ref "R11") (pin "2") (pinfunction "2_2") (pintype "passive"))
    )
    (net (code "62") (name "Net-(LED3-PadA)") (class "Default")
      (node (ref "LED3") (pin "A") (pinfunction "A_A") (pintype "passive"))
      (node (ref "R14") (pin "2") (pinfunction "2_2") (pintype "passive"))
    )
    (net (code "63") (name "Net-(LED4-PadA)") (class "Default")
      (node (ref "LED4") (pin "A") (pinfunction "A_A") (pintype "passive"))
      (node (ref "R21") (pin "1") (pinfunction "1_1") (pintype "passive"))
    )
    (net (code "64") (name "Net-(SW1-S)") (class "Default")
      (node (ref "R1") (pin "2") (pinfunction "2_2") (pintype "passive"))
      (node (ref "R2") (pin "1") (pinfunction "1_1") (pintype "passive"))
      (node (ref "R3") (pin "1") (pinfunction "1_1") (pintype "passive"))
      (node (ref "SW1") (pin "2") (pinfunction "S_2") (pintype "passive"))
    )
    (net (code "65") (name "unconnected-(DA1'-VREF-Pad5)") (class "Default")
      (node (ref "DA1'") (pin "5") (pinfunction "VREF_5") (pintype "passive"))
    )
    (net (code "66") (name "unconnected-(DD1-SUSPEND-Pad12)") (class "Default")
      (node (ref "DD1") (pin "12") (pinfunction "SUSPEND_12") (pintype "output"))
    )
    (net (code "67") (name "unconnected-(SWD-Pad6)") (class "Default")
      (node (ref "SWD") (pin "6") (pinfunction "6_6") (pintype "passive"))
    )
  )
)
